# HE6-RORO1.net
KiCad netlist of a schematic drawn in EAGLE
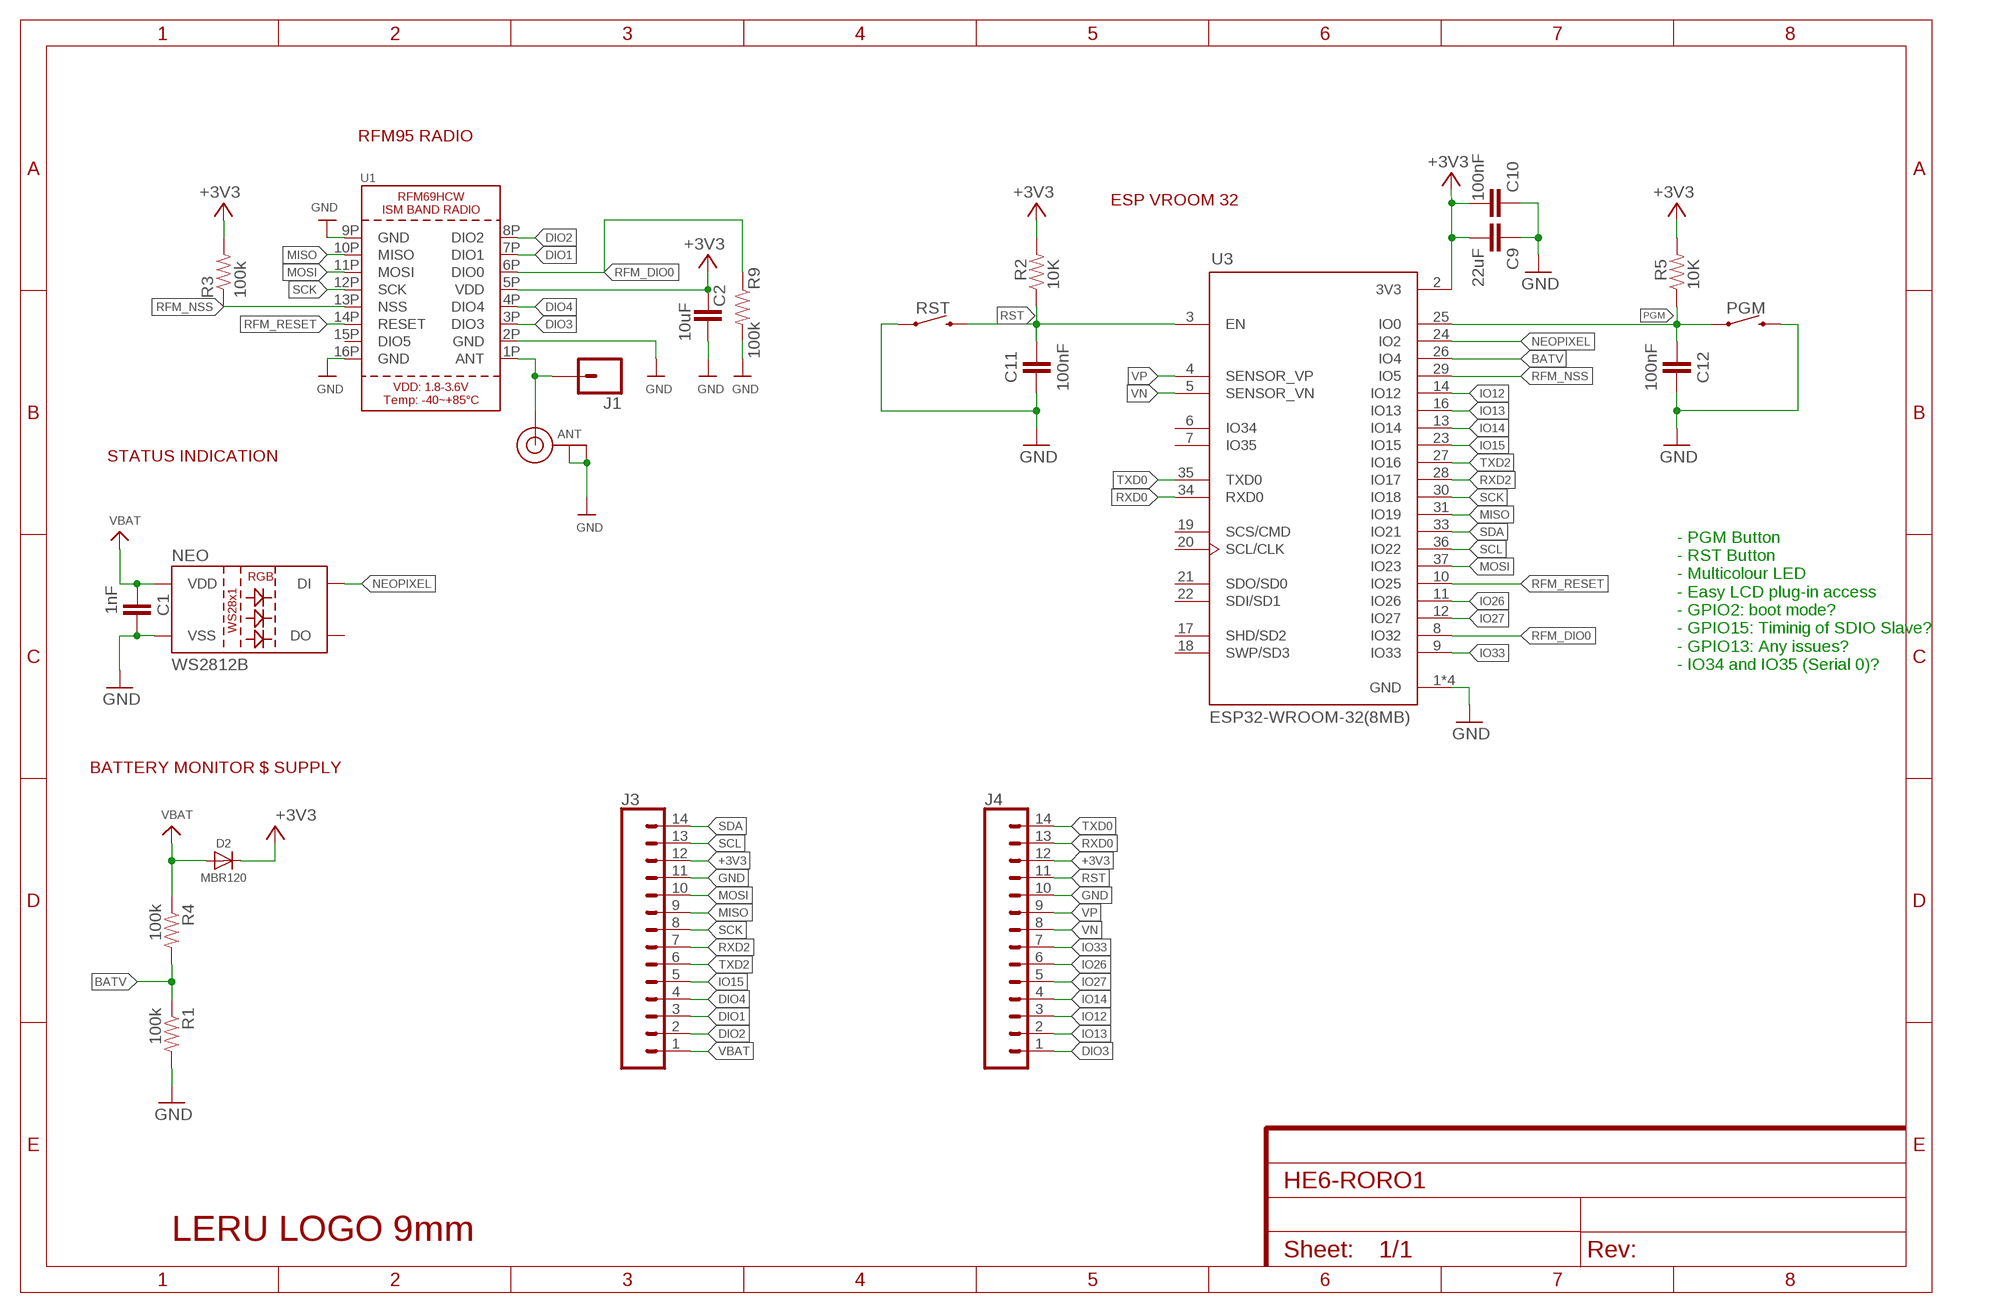
[diagram p0: schematic, sheet 1]

(export (version "E")
  (design (tool "Eeschema 10.0.6"))
  (components
    (comp (ref "ANT")
      (value "MICROBUILDER_ANTENNA_U.FL")
      (footprint "eagle-import:MICROBUILDER_U.FL")
      (libsource (lib "eagle-import") (part "MICROBUILDER_ANTENNA_U.FL"))
    )
    (comp (ref "C1")
      (value "1nF")
      (footprint "eagle-import:CAP")
      (libsource (lib "eagle-import") (part "CAP0805"))
    )
    (comp (ref "C2")
      (value "10uF")
      (footprint "eagle-import:CAP")
      (libsource (lib "eagle-import") (part "CAP0805"))
    )
    (comp (ref "C9")
      (value "22uF")
      (footprint "eagle-import:CAP")
      (libsource (lib "eagle-import") (part "CAP0805"))
    )
    (comp (ref "C10")
      (value "100nF")
      (footprint "eagle-import:CAP")
      (libsource (lib "eagle-import") (part "CAP0805"))
    )
    (comp (ref "C11")
      (value "100nF")
      (footprint "eagle-import:CAP")
      (libsource (lib "eagle-import") (part "CAP0805"))
    )
    (comp (ref "C12")
      (value "100nF")
      (footprint "eagle-import:CAP")
      (libsource (lib "eagle-import") (part "CAP0805"))
    )
    (comp (ref "D2")
      (value "MBR120")
      (footprint "eagle-import:DIODE")
      (libsource (lib "eagle-import") (part "DIODESOD123"))
    )
    (comp (ref "J1")
      (value "CONN_01PTH_NO_SILK_YES_STOP")
      (footprint "eagle-import:1X01_NO_SILK")
      (libsource (lib "eagle-import") (part "CONN_01PTH_NO_SILK_YES_STOP"))
    )
    (comp (ref "J3")
      (value "CONN_14NO_SILK")
      (footprint "eagle-import:1X14_NO_SILK")
      (libsource (lib "eagle-import") (part "CONN_14NO_SILK"))
    )
    (comp (ref "J4")
      (value "CONN_14NO_SILK")
      (footprint "eagle-import:1X14_NO_SILK")
      (libsource (lib "eagle-import") (part "CONN_14NO_SILK"))
    )
    (comp (ref "NEO")
      (value "WS2812B")
      (footprint "eagle-import:WS2812B")
      (libsource (lib "eagle-import") (part "WS2812B"))
    )
    (comp (ref "PGM")
      (value "MOMENTARY-SWITCH-SPST-SMD-6.0X3.5MM")
      (footprint "eagle-import:TACTILE_SWITCH_SMD_6.0X3.5MM")
      (libsource (lib "eagle-import") (part "MOMENTARY-SWITCH-SPST-SMD-6.0X3.5MM"))
    )
    (comp (ref "R1")
      (value "100k")
      (footprint "eagle-import:RES")
      (libsource (lib "eagle-import") (part "RES0805-RES"))
    )
    (comp (ref "R2")
      (value "10K")
      (footprint "eagle-import:RES")
      (libsource (lib "eagle-import") (part "RES0805-RES"))
    )
    (comp (ref "R3")
      (value "100k")
      (footprint "eagle-import:RES")
      (libsource (lib "eagle-import") (part "RES0805-RES"))
    )
    (comp (ref "R4")
      (value "100k")
      (footprint "eagle-import:RES")
      (libsource (lib "eagle-import") (part "RES0805-RES"))
    )
    (comp (ref "R5")
      (value "10K")
      (footprint "eagle-import:RES")
      (libsource (lib "eagle-import") (part "RES0805-RES"))
    )
    (comp (ref "R9")
      (value "100k")
      (footprint "eagle-import:RES")
      (libsource (lib "eagle-import") (part "RES0805-RES"))
    )
    (comp (ref "RST")
      (value "MOMENTARY-SWITCH-SPST-SMD-6.0X3.5MM")
      (footprint "eagle-import:TACTILE_SWITCH_SMD_6.0X3.5MM")
      (libsource (lib "eagle-import") (part "MOMENTARY-SWITCH-SPST-SMD-6.0X3.5MM"))
    )
    (comp (ref "U$9")
      (value "LERU_LOGO_9MM")
      (footprint "eagle-import:LERU_LOGO_9MM")
      (libsource (lib "eagle-import") (part "LERU_LOGO_9MM"))
    )
    (comp (ref "U1")
      (value "RFM69HCW_SMT")
      (footprint "eagle-import:RFMHCW_SMT")
      (libsource (lib "eagle-import") (part "RFM69HCW_SMT"))
    )
    (comp (ref "U3")
      (value "ESP32-WROOM-32(8MB)")
      (footprint "eagle-import:MODULE_ESP32-WROOM-32(8MB)")
      (fields (field (name "MF") "Espressif Systems") (field (name "MP") "ESP32-WROOM-32 _8MB_"))
      (libsource (lib "eagle-import") (part "ESP32-WROOM-32(8MB)"))
    )
  )
  (nets
    (net (code "1") (name "+3V3") (class "Default")
      (node (ref "C10") (pin "2") (pinfunction "2_2") (pintype "passive"))
      (node (ref "C2") (pin "1") (pinfunction "1_1") (pintype "passive"))
      (node (ref "C9") (pin "2") (pinfunction "2_2") (pintype "passive"))
      (node (ref "D2") (pin "1") (pinfunction "C_1") (pintype "passive"))
      (node (ref "J3") (pin "12") (pinfunction "12_12") (pintype "passive"))
      (node (ref "J4") (pin "12") (pinfunction "12_12") (pintype "passive"))
      (node (ref "R2") (pin "2") (pinfunction "2_2") (pintype "passive"))
      (node (ref "R3") (pin "2") (pinfunction "2_2") (pintype "passive"))
      (node (ref "R5") (pin "2") (pinfunction "2_2") (pintype "passive"))
      (node (ref "U1") (pin "5P") (pinfunction "VDD_5P") (pintype "power_in"))
      (node (ref "U3") (pin "2") (pinfunction "3V3_2") (pintype "power_in"))
    )
    (net (code "2") (name "BATV") (class "Default")
      (node (ref "R1") (pin "1") (pinfunction "1_1") (pintype "passive"))
      (node (ref "R4") (pin "2") (pinfunction "2_2") (pintype "passive"))
      (node (ref "U3") (pin "26") (pinfunction "IO4_26") (pintype "bidirectional"))
    )
    (net (code "3") (name "DIO1") (class "Default")
      (node (ref "J3") (pin "3") (pinfunction "3_3") (pintype "passive"))
      (node (ref "U1") (pin "7P") (pinfunction "DIO1_7P") (pintype "bidirectional"))
    )
    (net (code "4") (name "DIO2") (class "Default")
      (node (ref "J3") (pin "2") (pinfunction "2_2") (pintype "passive"))
      (node (ref "U1") (pin "8P") (pinfunction "DIO2_8P") (pintype "bidirectional"))
    )
    (net (code "5") (name "DIO3") (class "Default")
      (node (ref "J4") (pin "1") (pinfunction "1_1") (pintype "passive"))
      (node (ref "U1") (pin "3P") (pinfunction "DIO3_3P") (pintype "bidirectional"))
    )
    (net (code "6") (name "DIO4") (class "Default")
      (node (ref "J3") (pin "4") (pinfunction "4_4") (pintype "passive"))
      (node (ref "U1") (pin "4P") (pinfunction "DIO4_4P") (pintype "bidirectional"))
    )
    (net (code "7") (name "GND") (class "Default")
      (node (ref "ANT") (pin "1") (pinfunction "GND_1") (pintype "passive"))
      (node (ref "ANT") (pin "2") (pinfunction "GND_2") (pintype "passive"))
      (node (ref "C1") (pin "1") (pinfunction "1_1") (pintype "passive"))
      (node (ref "C10") (pin "1") (pinfunction "1_1") (pintype "passive"))
      (node (ref "C11") (pin "1") (pinfunction "1_1") (pintype "passive"))
      (node (ref "C12") (pin "1") (pinfunction "1_1") (pintype "passive"))
      (node (ref "C2") (pin "2") (pinfunction "2_2") (pintype "passive"))
      (node (ref "C9") (pin "1") (pinfunction "1_1") (pintype "passive"))
      (node (ref "J3") (pin "11") (pinfunction "11_11") (pintype "passive"))
      (node (ref "J4") (pin "10") (pinfunction "10_10") (pintype "passive"))
      (node (ref "NEO") (pin "3") (pinfunction "VSS_3") (pintype "bidirectional"))
      (node (ref "PGM") (pin "2") (pinfunction "2_2") (pintype "passive"))
      (node (ref "R1") (pin "2") (pinfunction "2_2") (pintype "passive"))
      (node (ref "R9") (pin "2") (pinfunction "2_2") (pintype "passive"))
      (node (ref "RST") (pin "1") (pinfunction "1_1") (pintype "passive"))
      (node (ref "U1") (pin "16P") (pinfunction "GND_16P") (pintype "power_in"))
      (node (ref "U1") (pin "2P") (pinfunction "GND_2P") (pintype "power_in"))
      (node (ref "U1") (pin "9P") (pinfunction "GND_9P") (pintype "power_in"))
      (node (ref "U3") (pin "1") (pinfunction "GND_1") (pintype "power_in"))
      (node (ref "U3") (pin "15") (pinfunction "GND_15") (pintype "power_in"))
      (node (ref "U3") (pin "38") (pinfunction "GND_38") (pintype "power_in"))
      (node (ref "U3") (pin "39") (pinfunction "GND_39") (pintype "power_in"))
    )
    (net (code "8") (name "IO12") (class "Default")
      (node (ref "J4") (pin "3") (pinfunction "3_3") (pintype "passive"))
      (node (ref "U3") (pin "14") (pinfunction "IO12_14") (pintype "bidirectional"))
    )
    (net (code "9") (name "IO13") (class "Default")
      (node (ref "J4") (pin "2") (pinfunction "2_2") (pintype "passive"))
      (node (ref "U3") (pin "16") (pinfunction "IO13_16") (pintype "bidirectional"))
    )
    (net (code "10") (name "IO14") (class "Default")
      (node (ref "J4") (pin "4") (pinfunction "4_4") (pintype "passive"))
      (node (ref "U3") (pin "13") (pinfunction "IO14_13") (pintype "bidirectional"))
    )
    (net (code "11") (name "IO15") (class "Default")
      (node (ref "J3") (pin "5") (pinfunction "5_5") (pintype "passive"))
      (node (ref "U3") (pin "23") (pinfunction "IO15_23") (pintype "bidirectional"))
    )
    (net (code "12") (name "IO26") (class "Default")
      (node (ref "J4") (pin "6") (pinfunction "6_6") (pintype "passive"))
      (node (ref "U3") (pin "11") (pinfunction "IO26_11") (pintype "bidirectional"))
    )
    (net (code "13") (name "IO27") (class "Default")
      (node (ref "J4") (pin "5") (pinfunction "5_5") (pintype "passive"))
      (node (ref "U3") (pin "12") (pinfunction "IO27_12") (pintype "bidirectional"))
    )
    (net (code "14") (name "IO33") (class "Default")
      (node (ref "J4") (pin "7") (pinfunction "7_7") (pintype "passive"))
      (node (ref "U3") (pin "9") (pinfunction "IO33_9") (pintype "bidirectional"))
    )
    (net (code "15") (name "MISO") (class "Default")
      (node (ref "J3") (pin "9") (pinfunction "9_9") (pintype "passive"))
      (node (ref "U1") (pin "10P") (pinfunction "MISO_10P") (pintype "output"))
      (node (ref "U3") (pin "31") (pinfunction "IO19_31") (pintype "bidirectional"))
    )
    (net (code "16") (name "MOSI") (class "Default")
      (node (ref "J3") (pin "10") (pinfunction "10_10") (pintype "passive"))
      (node (ref "U1") (pin "11P") (pinfunction "MOSI_11P") (pintype "input"))
      (node (ref "U3") (pin "37") (pinfunction "IO23_37") (pintype "bidirectional"))
    )
    (net (code "17") (name "NEOPIXEL") (class "Default")
      (node (ref "NEO") (pin "4") (pinfunction "DI_4") (pintype "bidirectional"))
      (node (ref "U3") (pin "24") (pinfunction "IO2_24") (pintype "bidirectional"))
    )
    (net (code "18") (name "Net-(ANT-SIGNAL)") (class "Default")
      (node (ref "ANT") (pin "3") (pinfunction "SIGNAL_3") (pintype "passive"))
      (node (ref "J1") (pin "1") (pinfunction "1_1") (pintype "passive"))
      (node (ref "U1") (pin "1P") (pinfunction "ANT_1P") (pintype "bidirectional"))
    )
    (net (code "19") (name "PGM") (class "Default")
      (node (ref "C12") (pin "2") (pinfunction "2_2") (pintype "passive"))
      (node (ref "PGM") (pin "1") (pinfunction "1_1") (pintype "passive"))
      (node (ref "R5") (pin "1") (pinfunction "1_1") (pintype "passive"))
      (node (ref "U3") (pin "25") (pinfunction "IO0_25") (pintype "bidirectional"))
    )
    (net (code "20") (name "RFM_DIO0") (class "Default")
      (node (ref "R9") (pin "1") (pinfunction "1_1") (pintype "passive"))
      (node (ref "U1") (pin "6P") (pinfunction "DIO0_6P") (pintype "bidirectional"))
      (node (ref "U3") (pin "8") (pinfunction "IO32_8") (pintype "bidirectional"))
    )
    (net (code "21") (name "RFM_NSS") (class "Default")
      (node (ref "R3") (pin "1") (pinfunction "1_1") (pintype "passive"))
      (node (ref "U1") (pin "13P") (pinfunction "NSS_13P") (pintype "input"))
      (node (ref "U3") (pin "29") (pinfunction "IO5_29") (pintype "bidirectional"))
    )
    (net (code "22") (name "RFM_RESET") (class "Default")
      (node (ref "U1") (pin "14P") (pinfunction "RESET_14P") (pintype "input"))
      (node (ref "U3") (pin "10") (pinfunction "IO25_10") (pintype "bidirectional"))
    )
    (net (code "23") (name "RST") (class "Default")
      (node (ref "C11") (pin "2") (pinfunction "2_2") (pintype "passive"))
      (node (ref "J4") (pin "11") (pinfunction "11_11") (pintype "passive"))
      (node (ref "R2") (pin "1") (pinfunction "1_1") (pintype "passive"))
      (node (ref "RST") (pin "2") (pinfunction "2_2") (pintype "passive"))
      (node (ref "U3") (pin "3") (pinfunction "EN_3") (pintype "input"))
    )
    (net (code "24") (name "RXD0") (class "Default")
      (node (ref "J4") (pin "13") (pinfunction "13_13") (pintype "passive"))
      (node (ref "U3") (pin "34") (pinfunction "RXD0_34") (pintype "bidirectional"))
    )
    (net (code "25") (name "RXD2") (class "Default")
      (node (ref "J3") (pin "7") (pinfunction "7_7") (pintype "passive"))
      (node (ref "U3") (pin "28") (pinfunction "IO17_28") (pintype "bidirectional"))
    )
    (net (code "26") (name "SCK") (class "Default")
      (node (ref "J3") (pin "8") (pinfunction "8_8") (pintype "passive"))
      (node (ref "U1") (pin "12P") (pinfunction "SCK_12P") (pintype "input"))
      (node (ref "U3") (pin "30") (pinfunction "IO18_30") (pintype "bidirectional"))
    )
    (net (code "27") (name "SCL") (class "Default")
      (node (ref "J3") (pin "13") (pinfunction "13_13") (pintype "passive"))
      (node (ref "U3") (pin "36") (pinfunction "IO22_36") (pintype "bidirectional"))
    )
    (net (code "28") (name "SDA") (class "Default")
      (node (ref "J3") (pin "14") (pinfunction "14_14") (pintype "passive"))
      (node (ref "U3") (pin "33") (pinfunction "IO21_33") (pintype "bidirectional"))
    )
    (net (code "29") (name "TXD0") (class "Default")
      (node (ref "J4") (pin "14") (pinfunction "14_14") (pintype "passive"))
      (node (ref "U3") (pin "35") (pinfunction "TXD0_35") (pintype "bidirectional"))
    )
    (net (code "30") (name "TXD2") (class "Default")
      (node (ref "J3") (pin "6") (pinfunction "6_6") (pintype "passive"))
      (node (ref "U3") (pin "27") (pinfunction "IO16_27") (pintype "bidirectional"))
    )
    (net (code "31") (name "VBAT") (class "Default")
      (node (ref "C1") (pin "2") (pinfunction "2_2") (pintype "passive"))
      (node (ref "D2") (pin "2") (pinfunction "A_2") (pintype "passive"))
      (node (ref "J3") (pin "1") (pinfunction "1_1") (pintype "passive"))
      (node (ref "NEO") (pin "1") (pinfunction "VDD_1") (pintype "bidirectional"))
      (node (ref "R4") (pin "1") (pinfunction "1_1") (pintype "passive"))
    )
    (net (code "32") (name "VN") (class "Default")
      (node (ref "J4") (pin "8") (pinfunction "8_8") (pintype "passive"))
      (node (ref "U3") (pin "5") (pinfunction "SENSOR_VN_5") (pintype "input"))
    )
    (net (code "33") (name "VP") (class "Default")
      (node (ref "J4") (pin "9") (pinfunction "9_9") (pintype "passive"))
      (node (ref "U3") (pin "4") (pinfunction "SENSOR_VP_4") (pintype "input"))
    )
    (net (code "34") (name "unconnected-(NEO-DO-Pad2)") (class "Default")
      (node (ref "NEO") (pin "2") (pinfunction "DO_2") (pintype "bidirectional"))
    )
    (net (code "35") (name "unconnected-(U1-DIO5-Pad15P)") (class "Default")
      (node (ref "U1") (pin "15P") (pinfunction "DIO5_15P") (pintype "bidirectional"))
    )
    (net (code "36") (name "unconnected-(U3-IO34-Pad6)") (class "Default")
      (node (ref "U3") (pin "6") (pinfunction "IO34_6") (pintype "input"))
    )
    (net (code "37") (name "unconnected-(U3-IO35-Pad7)") (class "Default")
      (node (ref "U3") (pin "7") (pinfunction "IO35_7") (pintype "input"))
    )
    (net (code "38") (name "unconnected-(U3-SCL{slash}CLK-Pad20)") (class "Default")
      (node (ref "U3") (pin "20") (pinfunction "SCL/CLK_20") (pintype "bidirectional"))
    )
    (net (code "39") (name "unconnected-(U3-SCS{slash}CMD-Pad19)") (class "Default")
      (node (ref "U3") (pin "19") (pinfunction "SCS/CMD_19") (pintype "bidirectional"))
    )
    (net (code "40") (name "unconnected-(U3-SDI{slash}SD1-Pad22)") (class "Default")
      (node (ref "U3") (pin "22") (pinfunction "SDI/SD1_22") (pintype "bidirectional"))
    )
    (net (code "41") (name "unconnected-(U3-SDO{slash}SD0-Pad21)") (class "Default")
      (node (ref "U3") (pin "21") (pinfunction "SDO/SD0_21") (pintype "bidirectional"))
    )
    (net (code "42") (name "unconnected-(U3-SHD{slash}SD2-Pad17)") (class "Default")
      (node (ref "U3") (pin "17") (pinfunction "SHD/SD2_17") (pintype "bidirectional"))
    )
    (net (code "43") (name "unconnected-(U3-SWP{slash}SD3-Pad18)") (class "Default")
      (node (ref "U3") (pin "18") (pinfunction "SWP/SD3_18") (pintype "bidirectional"))
    )
  )
)
